# lamloei_app_a092500.net
KiCad netlist of a schematic drawn in EAGLE
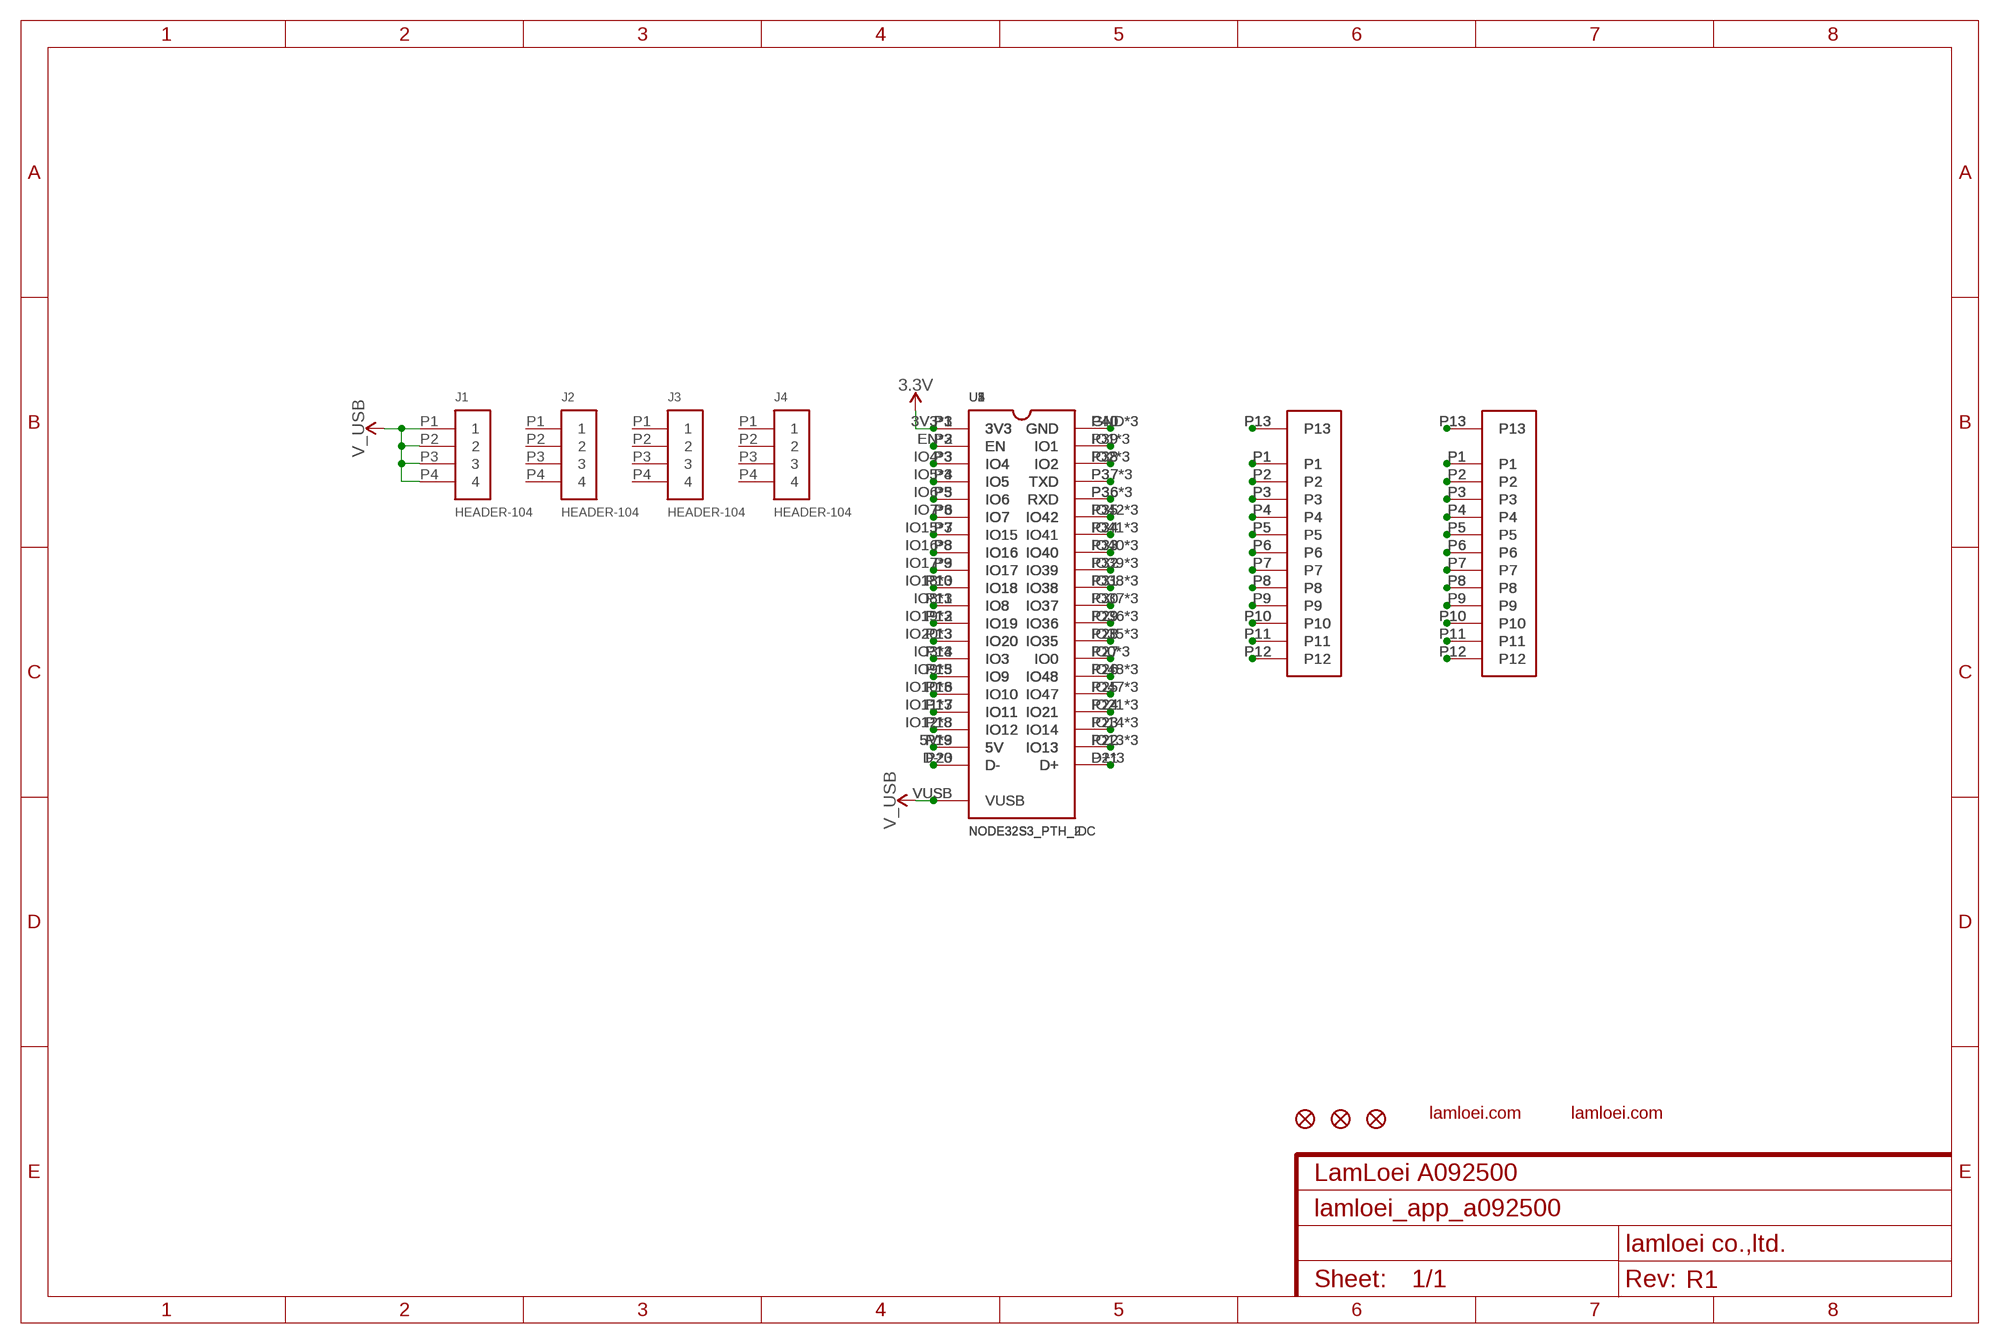
[diagram p0: schematic, sheet 1]

(export (version "E")
  (design (tool "Eeschema 10.0.6"))
  (components
    (comp (ref "J1")
      (value "HEADER-104")
      (footprint "eagle-import:HEADER-104")
      (libsource (lib "eagle-import") (part "HEADER-104"))
    )
    (comp (ref "J2")
      (value "HEADER-104")
      (footprint "eagle-import:HEADER-104")
      (libsource (lib "eagle-import") (part "HEADER-104"))
    )
    (comp (ref "J3")
      (value "HEADER-104")
      (footprint "eagle-import:HEADER-104")
      (libsource (lib "eagle-import") (part "HEADER-104"))
    )
    (comp (ref "J4")
      (value "HEADER-104")
      (footprint "eagle-import:HEADER-104")
      (libsource (lib "eagle-import") (part "HEADER-104"))
    )
    (comp (ref "U1")
      (value "NODE32S3_PTH_2")
      (footprint "eagle-import:NODE32S3_PTH_2")
      (libsource (lib "eagle-import") (part "NODE32S3_PTH_2"))
    )
    (comp (ref "U2")
      (value "NODE32S3_PTH_2")
      (footprint "eagle-import:NODE32S3_PTH_2")
      (libsource (lib "eagle-import") (part "NODE32S3_PTH_2"))
    )
    (comp (ref "U3")
      (value "NODE32S3_PTH_IDC")
      (footprint "eagle-import:NODE32S3_PTH_IDC")
      (libsource (lib "eagle-import") (part "NODE32S3_PTH_IDC"))
    )
    (comp (ref "U4")
      (value "NODE32S3_PTH_IDC")
      (footprint "eagle-import:NODE32S3_PTH_IDC")
      (libsource (lib "eagle-import") (part "NODE32S3_PTH_IDC"))
    )
    (comp (ref "U5")
      (value "NODE32S3_PTH_IDC")
      (footprint "eagle-import:NODE32S3_PTH_IDC")
      (libsource (lib "eagle-import") (part "NODE32S3_PTH_IDC"))
    )
    (comp (ref "X1")
      (value "5EHDRC-12P")
      (footprint "eagle-import:5EHDRC-12P")
      (libsource (lib "eagle-import") (part "5EHDRC-12P"))
    )
    (comp (ref "X2")
      (value "5EHDRC-12P-5.08MM")
      (footprint "eagle-import:5EHDRC-12P-5.08MM")
      (libsource (lib "eagle-import") (part "5EHDRC-12P-5.08MM"))
    )
    (comp (ref "X3")
      (value "5EHDRC-12P-2")
      (footprint "eagle-import:5EHDRC-12P-2")
      (libsource (lib "eagle-import") (part "5EHDRC-12P-2"))
    )
    (comp (ref "X4")
      (value "5EHDRC-12P")
      (footprint "eagle-import:5EHDRC-12P")
      (libsource (lib "eagle-import") (part "5EHDRC-12P"))
    )
    (comp (ref "X5")
      (value "5EHDRC-12P-5.08MM")
      (footprint "eagle-import:5EHDRC-12P-5.08MM")
      (libsource (lib "eagle-import") (part "5EHDRC-12P-5.08MM"))
    )
    (comp (ref "X6")
      (value "5EHDRC-12P-2")
      (footprint "eagle-import:5EHDRC-12P-2")
      (libsource (lib "eagle-import") (part "5EHDRC-12P-2"))
    )
    (comp (ref "ZFD1")
      (value "FIDUCIAL1X2")
      (footprint "eagle-import:FIDUCIAL-1X2")
      (libsource (lib "eagle-import") (part "FIDUCIAL1X2"))
    )
    (comp (ref "ZFD2")
      (value "FIDUCIAL1X2")
      (footprint "eagle-import:FIDUCIAL-1X2")
      (libsource (lib "eagle-import") (part "FIDUCIAL1X2"))
    )
    (comp (ref "ZFD3")
      (value "FIDUCIAL1X2")
      (footprint "eagle-import:FIDUCIAL-1X2")
      (libsource (lib "eagle-import") (part "FIDUCIAL1X2"))
    )
    (comp (ref "ZL1")
      (value "LAMLEOI_LOGO_3")
      (footprint "eagle-import:LAMLEOI_LOGO_3")
      (libsource (lib "eagle-import") (part "LAMLEOI_LOGO_3"))
    )
    (comp (ref "ZL2")
      (value "LAMLEOI_LOGO_3")
      (footprint "eagle-import:LAMLEOI_LOGO_3")
      (libsource (lib "eagle-import") (part "LAMLEOI_LOGO_3"))
    )
  )
  (nets
    (net (code "1") (name "3.3V") (class "Default")
      (node (ref "U1") (pin "3V3") (pinfunction "3V3_3V3") (pintype "bidirectional"))
      (node (ref "U1") (pin "P1") (pinfunction "3V3_P1") (pintype "bidirectional"))
      (node (ref "U1") (pin "Q1") (pinfunction "3V3_Q1") (pintype "bidirectional"))
      (node (ref "U2") (pin "3V3") (pinfunction "3V3_3V3") (pintype "bidirectional"))
      (node (ref "U2") (pin "P1") (pinfunction "3V3_P1") (pintype "bidirectional"))
      (node (ref "U2") (pin "Q1") (pinfunction "3V3_Q1") (pintype "bidirectional"))
      (node (ref "U3") (pin "P1") (pinfunction "3V3_P1") (pintype "bidirectional"))
      (node (ref "U4") (pin "P1") (pinfunction "3V3_P1") (pintype "bidirectional"))
      (node (ref "U5") (pin "P1") (pinfunction "3V3_P1") (pintype "bidirectional"))
    )
    (net (code "2") (name "Net-(U3-5V)") (class "Default")
      (node (ref "U1") (pin "5V") (pinfunction "5V_5V") (pintype "bidirectional"))
      (node (ref "U1") (pin "P19") (pinfunction "5V_P19") (pintype "bidirectional"))
      (node (ref "U1") (pin "Q19") (pinfunction "5V_Q19") (pintype "bidirectional"))
      (node (ref "U2") (pin "5V") (pinfunction "5V_5V") (pintype "bidirectional"))
      (node (ref "U2") (pin "P19") (pinfunction "5V_P19") (pintype "bidirectional"))
      (node (ref "U2") (pin "Q19") (pinfunction "5V_Q19") (pintype "bidirectional"))
      (node (ref "U3") (pin "P19") (pinfunction "5V_P19") (pintype "bidirectional"))
      (node (ref "U4") (pin "P19") (pinfunction "5V_P19") (pintype "bidirectional"))
      (node (ref "U5") (pin "P19") (pinfunction "5V_P19") (pintype "bidirectional"))
    )
    (net (code "3") (name "Net-(U3-D+)") (class "Default")
      (node (ref "U1") (pin "D+") (pinfunction "D+_D+") (pintype "bidirectional"))
      (node (ref "U1") (pin "P21") (pinfunction "D+_P21") (pintype "bidirectional"))
      (node (ref "U1") (pin "Q21") (pinfunction "D+_Q21") (pintype "bidirectional"))
      (node (ref "U2") (pin "D+") (pinfunction "D+_D+") (pintype "bidirectional"))
      (node (ref "U2") (pin "P21") (pinfunction "D+_P21") (pintype "bidirectional"))
      (node (ref "U2") (pin "Q21") (pinfunction "D+_Q21") (pintype "bidirectional"))
      (node (ref "U3") (pin "P21") (pinfunction "D+_P21") (pintype "bidirectional"))
      (node (ref "U4") (pin "P21") (pinfunction "D+_P21") (pintype "bidirectional"))
      (node (ref "U5") (pin "P21") (pinfunction "D+_P21") (pintype "bidirectional"))
    )
    (net (code "4") (name "Net-(U3-D-)") (class "Default")
      (node (ref "U1") (pin "D-") (pinfunction "D-_D-") (pintype "bidirectional"))
      (node (ref "U1") (pin "P20") (pinfunction "D-_P20") (pintype "bidirectional"))
      (node (ref "U1") (pin "Q20") (pinfunction "D-_Q20") (pintype "bidirectional"))
      (node (ref "U2") (pin "D-") (pinfunction "D-_D-") (pintype "bidirectional"))
      (node (ref "U2") (pin "P20") (pinfunction "D-_P20") (pintype "bidirectional"))
      (node (ref "U2") (pin "Q20") (pinfunction "D-_Q20") (pintype "bidirectional"))
      (node (ref "U3") (pin "P20") (pinfunction "D-_P20") (pintype "bidirectional"))
      (node (ref "U4") (pin "P20") (pinfunction "D-_P20") (pintype "bidirectional"))
      (node (ref "U5") (pin "P20") (pinfunction "D-_P20") (pintype "bidirectional"))
    )
    (net (code "5") (name "Net-(U3-EN)") (class "Default")
      (node (ref "U1") (pin "EN") (pinfunction "EN_EN") (pintype "bidirectional"))
      (node (ref "U1") (pin "P2") (pinfunction "EN_P2") (pintype "bidirectional"))
      (node (ref "U1") (pin "Q2") (pinfunction "EN_Q2") (pintype "bidirectional"))
      (node (ref "U2") (pin "EN") (pinfunction "EN_EN") (pintype "bidirectional"))
      (node (ref "U2") (pin "P2") (pinfunction "EN_P2") (pintype "bidirectional"))
      (node (ref "U2") (pin "Q2") (pinfunction "EN_Q2") (pintype "bidirectional"))
      (node (ref "U3") (pin "P2") (pinfunction "EN_P2") (pintype "bidirectional"))
      (node (ref "U4") (pin "P2") (pinfunction "EN_P2") (pintype "bidirectional"))
      (node (ref "U5") (pin "P2") (pinfunction "EN_P2") (pintype "bidirectional"))
    )
    (net (code "6") (name "Net-(U3-GND)") (class "Default")
      (node (ref "U1") (pin "GND") (pinfunction "GND_GND") (pintype "bidirectional"))
      (node (ref "U1") (pin "P40") (pinfunction "GND_P40") (pintype "bidirectional"))
      (node (ref "U1") (pin "Q40") (pinfunction "GND_Q40") (pintype "bidirectional"))
      (node (ref "U2") (pin "GND") (pinfunction "GND_GND") (pintype "bidirectional"))
      (node (ref "U2") (pin "P40") (pinfunction "GND_P40") (pintype "bidirectional"))
      (node (ref "U2") (pin "Q40") (pinfunction "GND_Q40") (pintype "bidirectional"))
      (node (ref "U3") (pin "P40") (pinfunction "GND_P40") (pintype "bidirectional"))
      (node (ref "U4") (pin "P40") (pinfunction "GND_P40") (pintype "bidirectional"))
      (node (ref "U5") (pin "P40") (pinfunction "GND_P40") (pintype "bidirectional"))
    )
    (net (code "7") (name "Net-(U3-IO0)") (class "Default")
      (node (ref "U1") (pin "IO0") (pinfunction "IO0_IO0") (pintype "bidirectional"))
      (node (ref "U1") (pin "P27") (pinfunction "IO0_P27") (pintype "bidirectional"))
      (node (ref "U1") (pin "Q27") (pinfunction "IO0_Q27") (pintype "bidirectional"))
      (node (ref "U2") (pin "IO0") (pinfunction "IO0_IO0") (pintype "bidirectional"))
      (node (ref "U2") (pin "P27") (pinfunction "IO0_P27") (pintype "bidirectional"))
      (node (ref "U2") (pin "Q27") (pinfunction "IO0_Q27") (pintype "bidirectional"))
      (node (ref "U3") (pin "P27") (pinfunction "IO0_P27") (pintype "bidirectional"))
      (node (ref "U4") (pin "P27") (pinfunction "IO0_P27") (pintype "bidirectional"))
      (node (ref "U5") (pin "P27") (pinfunction "IO0_P27") (pintype "bidirectional"))
    )
    (net (code "8") (name "Net-(U3-IO1)") (class "Default")
      (node (ref "U1") (pin "IO1") (pinfunction "IO1_IO1") (pintype "bidirectional"))
      (node (ref "U1") (pin "P39") (pinfunction "IO1_P39") (pintype "bidirectional"))
      (node (ref "U1") (pin "Q39") (pinfunction "IO1_Q39") (pintype "bidirectional"))
      (node (ref "U2") (pin "IO1") (pinfunction "IO1_IO1") (pintype "bidirectional"))
      (node (ref "U2") (pin "P39") (pinfunction "IO1_P39") (pintype "bidirectional"))
      (node (ref "U2") (pin "Q39") (pinfunction "IO1_Q39") (pintype "bidirectional"))
      (node (ref "U3") (pin "P39") (pinfunction "IO1_P39") (pintype "bidirectional"))
      (node (ref "U4") (pin "P39") (pinfunction "IO1_P39") (pintype "bidirectional"))
      (node (ref "U5") (pin "P39") (pinfunction "IO1_P39") (pintype "bidirectional"))
    )
    (net (code "9") (name "Net-(U3-IO2)") (class "Default")
      (node (ref "U1") (pin "IO2") (pinfunction "IO2_IO2") (pintype "bidirectional"))
      (node (ref "U1") (pin "P38") (pinfunction "IO2_P38") (pintype "bidirectional"))
      (node (ref "U1") (pin "Q38") (pinfunction "IO2_Q38") (pintype "bidirectional"))
      (node (ref "U2") (pin "IO2") (pinfunction "IO2_IO2") (pintype "bidirectional"))
      (node (ref "U2") (pin "P38") (pinfunction "IO2_P38") (pintype "bidirectional"))
      (node (ref "U2") (pin "Q38") (pinfunction "IO2_Q38") (pintype "bidirectional"))
      (node (ref "U3") (pin "P38") (pinfunction "IO2_P38") (pintype "bidirectional"))
      (node (ref "U4") (pin "P38") (pinfunction "IO2_P38") (pintype "bidirectional"))
      (node (ref "U5") (pin "P38") (pinfunction "IO2_P38") (pintype "bidirectional"))
    )
    (net (code "10") (name "Net-(U3-IO3)") (class "Default")
      (node (ref "U1") (pin "IO3") (pinfunction "IO3_IO3") (pintype "bidirectional"))
      (node (ref "U1") (pin "P14") (pinfunction "IO3_P14") (pintype "bidirectional"))
      (node (ref "U1") (pin "Q14") (pinfunction "IO3_Q14") (pintype "bidirectional"))
      (node (ref "U2") (pin "IO3") (pinfunction "IO3_IO3") (pintype "bidirectional"))
      (node (ref "U2") (pin "P14") (pinfunction "IO3_P14") (pintype "bidirectional"))
      (node (ref "U2") (pin "Q14") (pinfunction "IO3_Q14") (pintype "bidirectional"))
      (node (ref "U3") (pin "P14") (pinfunction "IO3_P14") (pintype "bidirectional"))
      (node (ref "U4") (pin "P14") (pinfunction "IO3_P14") (pintype "bidirectional"))
      (node (ref "U5") (pin "P14") (pinfunction "IO3_P14") (pintype "bidirectional"))
    )
    (net (code "11") (name "Net-(U3-IO4)") (class "Default")
      (node (ref "U1") (pin "IO4") (pinfunction "IO4_IO4") (pintype "bidirectional"))
      (node (ref "U1") (pin "P3") (pinfunction "IO4_P3") (pintype "bidirectional"))
      (node (ref "U1") (pin "Q3") (pinfunction "IO4_Q3") (pintype "bidirectional"))
      (node (ref "U2") (pin "IO4") (pinfunction "IO4_IO4") (pintype "bidirectional"))
      (node (ref "U2") (pin "P3") (pinfunction "IO4_P3") (pintype "bidirectional"))
      (node (ref "U2") (pin "Q3") (pinfunction "IO4_Q3") (pintype "bidirectional"))
      (node (ref "U3") (pin "P3") (pinfunction "IO4_P3") (pintype "bidirectional"))
      (node (ref "U4") (pin "P3") (pinfunction "IO4_P3") (pintype "bidirectional"))
      (node (ref "U5") (pin "P3") (pinfunction "IO4_P3") (pintype "bidirectional"))
    )
    (net (code "12") (name "Net-(U3-IO5)") (class "Default")
      (node (ref "U1") (pin "IO5") (pinfunction "IO5_IO5") (pintype "bidirectional"))
      (node (ref "U1") (pin "P4") (pinfunction "IO5_P4") (pintype "bidirectional"))
      (node (ref "U1") (pin "Q4") (pinfunction "IO5_Q4") (pintype "bidirectional"))
      (node (ref "U2") (pin "IO5") (pinfunction "IO5_IO5") (pintype "bidirectional"))
      (node (ref "U2") (pin "P4") (pinfunction "IO5_P4") (pintype "bidirectional"))
      (node (ref "U2") (pin "Q4") (pinfunction "IO5_Q4") (pintype "bidirectional"))
      (node (ref "U3") (pin "P4") (pinfunction "IO5_P4") (pintype "bidirectional"))
      (node (ref "U4") (pin "P4") (pinfunction "IO5_P4") (pintype "bidirectional"))
      (node (ref "U5") (pin "P4") (pinfunction "IO5_P4") (pintype "bidirectional"))
    )
    (net (code "13") (name "Net-(U3-IO6)") (class "Default")
      (node (ref "U1") (pin "IO6") (pinfunction "IO6_IO6") (pintype "bidirectional"))
      (node (ref "U1") (pin "P5") (pinfunction "IO6_P5") (pintype "bidirectional"))
      (node (ref "U1") (pin "Q5") (pinfunction "IO6_Q5") (pintype "bidirectional"))
      (node (ref "U2") (pin "IO6") (pinfunction "IO6_IO6") (pintype "bidirectional"))
      (node (ref "U2") (pin "P5") (pinfunction "IO6_P5") (pintype "bidirectional"))
      (node (ref "U2") (pin "Q5") (pinfunction "IO6_Q5") (pintype "bidirectional"))
      (node (ref "U3") (pin "P5") (pinfunction "IO6_P5") (pintype "bidirectional"))
      (node (ref "U4") (pin "P5") (pinfunction "IO6_P5") (pintype "bidirectional"))
      (node (ref "U5") (pin "P5") (pinfunction "IO6_P5") (pintype "bidirectional"))
    )
    (net (code "14") (name "Net-(U3-IO7)") (class "Default")
      (node (ref "U1") (pin "IO7") (pinfunction "IO7_IO7") (pintype "bidirectional"))
      (node (ref "U1") (pin "P6") (pinfunction "IO7_P6") (pintype "bidirectional"))
      (node (ref "U1") (pin "Q6") (pinfunction "IO7_Q6") (pintype "bidirectional"))
      (node (ref "U2") (pin "IO7") (pinfunction "IO7_IO7") (pintype "bidirectional"))
      (node (ref "U2") (pin "P6") (pinfunction "IO7_P6") (pintype "bidirectional"))
      (node (ref "U2") (pin "Q6") (pinfunction "IO7_Q6") (pintype "bidirectional"))
      (node (ref "U3") (pin "P6") (pinfunction "IO7_P6") (pintype "bidirectional"))
      (node (ref "U4") (pin "P6") (pinfunction "IO7_P6") (pintype "bidirectional"))
      (node (ref "U5") (pin "P6") (pinfunction "IO7_P6") (pintype "bidirectional"))
    )
    (net (code "15") (name "Net-(U3-IO8)") (class "Default")
      (node (ref "U1") (pin "IO8") (pinfunction "IO8_IO8") (pintype "bidirectional"))
      (node (ref "U1") (pin "P11") (pinfunction "IO8_P11") (pintype "bidirectional"))
      (node (ref "U1") (pin "Q11") (pinfunction "IO8_Q11") (pintype "bidirectional"))
      (node (ref "U2") (pin "IO8") (pinfunction "IO8_IO8") (pintype "bidirectional"))
      (node (ref "U2") (pin "P11") (pinfunction "IO8_P11") (pintype "bidirectional"))
      (node (ref "U2") (pin "Q11") (pinfunction "IO8_Q11") (pintype "bidirectional"))
      (node (ref "U3") (pin "P11") (pinfunction "IO8_P11") (pintype "bidirectional"))
      (node (ref "U4") (pin "P11") (pinfunction "IO8_P11") (pintype "bidirectional"))
      (node (ref "U5") (pin "P11") (pinfunction "IO8_P11") (pintype "bidirectional"))
    )
    (net (code "16") (name "Net-(U3-IO9)") (class "Default")
      (node (ref "U1") (pin "IO9") (pinfunction "IO9_IO9") (pintype "bidirectional"))
      (node (ref "U1") (pin "P15") (pinfunction "IO9_P15") (pintype "bidirectional"))
      (node (ref "U1") (pin "Q15") (pinfunction "IO9_Q15") (pintype "bidirectional"))
      (node (ref "U2") (pin "IO9") (pinfunction "IO9_IO9") (pintype "bidirectional"))
      (node (ref "U2") (pin "P15") (pinfunction "IO9_P15") (pintype "bidirectional"))
      (node (ref "U2") (pin "Q15") (pinfunction "IO9_Q15") (pintype "bidirectional"))
      (node (ref "U3") (pin "P15") (pinfunction "IO9_P15") (pintype "bidirectional"))
      (node (ref "U4") (pin "P15") (pinfunction "IO9_P15") (pintype "bidirectional"))
      (node (ref "U5") (pin "P15") (pinfunction "IO9_P15") (pintype "bidirectional"))
    )
    (net (code "17") (name "Net-(U3-IO10)") (class "Default")
      (node (ref "U1") (pin "IO10") (pinfunction "IO10_IO10") (pintype "bidirectional"))
      (node (ref "U1") (pin "P16") (pinfunction "IO10_P16") (pintype "bidirectional"))
      (node (ref "U1") (pin "Q16") (pinfunction "IO10_Q16") (pintype "bidirectional"))
      (node (ref "U2") (pin "IO10") (pinfunction "IO10_IO10") (pintype "bidirectional"))
      (node (ref "U2") (pin "P16") (pinfunction "IO10_P16") (pintype "bidirectional"))
      (node (ref "U2") (pin "Q16") (pinfunction "IO10_Q16") (pintype "bidirectional"))
      (node (ref "U3") (pin "P16") (pinfunction "IO10_P16") (pintype "bidirectional"))
      (node (ref "U4") (pin "P16") (pinfunction "IO10_P16") (pintype "bidirectional"))
      (node (ref "U5") (pin "P16") (pinfunction "IO10_P16") (pintype "bidirectional"))
    )
    (net (code "18") (name "Net-(U3-IO11)") (class "Default")
      (node (ref "U1") (pin "IO11") (pinfunction "IO11_IO11") (pintype "bidirectional"))
      (node (ref "U1") (pin "P17") (pinfunction "IO11_P17") (pintype "bidirectional"))
      (node (ref "U1") (pin "Q17") (pinfunction "IO11_Q17") (pintype "bidirectional"))
      (node (ref "U2") (pin "IO11") (pinfunction "IO11_IO11") (pintype "bidirectional"))
      (node (ref "U2") (pin "P17") (pinfunction "IO11_P17") (pintype "bidirectional"))
      (node (ref "U2") (pin "Q17") (pinfunction "IO11_Q17") (pintype "bidirectional"))
      (node (ref "U3") (pin "P17") (pinfunction "IO11_P17") (pintype "bidirectional"))
      (node (ref "U4") (pin "P17") (pinfunction "IO11_P17") (pintype "bidirectional"))
      (node (ref "U5") (pin "P17") (pinfunction "IO11_P17") (pintype "bidirectional"))
    )
    (net (code "19") (name "Net-(U3-IO12)") (class "Default")
      (node (ref "U1") (pin "IO12") (pinfunction "IO12_IO12") (pintype "bidirectional"))
      (node (ref "U1") (pin "P18") (pinfunction "IO12_P18") (pintype "bidirectional"))
      (node (ref "U1") (pin "Q18") (pinfunction "IO12_Q18") (pintype "bidirectional"))
      (node (ref "U2") (pin "IO12") (pinfunction "IO12_IO12") (pintype "bidirectional"))
      (node (ref "U2") (pin "P18") (pinfunction "IO12_P18") (pintype "bidirectional"))
      (node (ref "U2") (pin "Q18") (pinfunction "IO12_Q18") (pintype "bidirectional"))
      (node (ref "U3") (pin "P18") (pinfunction "IO12_P18") (pintype "bidirectional"))
      (node (ref "U4") (pin "P18") (pinfunction "IO12_P18") (pintype "bidirectional"))
      (node (ref "U5") (pin "P18") (pinfunction "IO12_P18") (pintype "bidirectional"))
    )
    (net (code "20") (name "Net-(U3-IO13)") (class "Default")
      (node (ref "U1") (pin "IO13") (pinfunction "IO13_IO13") (pintype "bidirectional"))
      (node (ref "U1") (pin "P22") (pinfunction "IO13_P22") (pintype "bidirectional"))
      (node (ref "U1") (pin "Q22") (pinfunction "IO13_Q22") (pintype "bidirectional"))
      (node (ref "U2") (pin "IO13") (pinfunction "IO13_IO13") (pintype "bidirectional"))
      (node (ref "U2") (pin "P22") (pinfunction "IO13_P22") (pintype "bidirectional"))
      (node (ref "U2") (pin "Q22") (pinfunction "IO13_Q22") (pintype "bidirectional"))
      (node (ref "U3") (pin "P22") (pinfunction "IO13_P22") (pintype "bidirectional"))
      (node (ref "U4") (pin "P22") (pinfunction "IO13_P22") (pintype "bidirectional"))
      (node (ref "U5") (pin "P22") (pinfunction "IO13_P22") (pintype "bidirectional"))
    )
    (net (code "21") (name "Net-(U3-IO14)") (class "Default")
      (node (ref "U1") (pin "IO14") (pinfunction "IO14_IO14") (pintype "bidirectional"))
      (node (ref "U1") (pin "P23") (pinfunction "IO14_P23") (pintype "bidirectional"))
      (node (ref "U1") (pin "Q23") (pinfunction "IO14_Q23") (pintype "bidirectional"))
      (node (ref "U2") (pin "IO14") (pinfunction "IO14_IO14") (pintype "bidirectional"))
      (node (ref "U2") (pin "P23") (pinfunction "IO14_P23") (pintype "bidirectional"))
      (node (ref "U2") (pin "Q23") (pinfunction "IO14_Q23") (pintype "bidirectional"))
      (node (ref "U3") (pin "P23") (pinfunction "IO14_P23") (pintype "bidirectional"))
      (node (ref "U4") (pin "P23") (pinfunction "IO14_P23") (pintype "bidirectional"))
      (node (ref "U5") (pin "P23") (pinfunction "IO14_P23") (pintype "bidirectional"))
    )
    (net (code "22") (name "Net-(U3-IO15)") (class "Default")
      (node (ref "U1") (pin "IO15") (pinfunction "IO15_IO15") (pintype "bidirectional"))
      (node (ref "U1") (pin "P7") (pinfunction "IO15_P7") (pintype "bidirectional"))
      (node (ref "U1") (pin "Q7") (pinfunction "IO15_Q7") (pintype "bidirectional"))
      (node (ref "U2") (pin "IO15") (pinfunction "IO15_IO15") (pintype "bidirectional"))
      (node (ref "U2") (pin "P7") (pinfunction "IO15_P7") (pintype "bidirectional"))
      (node (ref "U2") (pin "Q7") (pinfunction "IO15_Q7") (pintype "bidirectional"))
      (node (ref "U3") (pin "P7") (pinfunction "IO15_P7") (pintype "bidirectional"))
      (node (ref "U4") (pin "P7") (pinfunction "IO15_P7") (pintype "bidirectional"))
      (node (ref "U5") (pin "P7") (pinfunction "IO15_P7") (pintype "bidirectional"))
    )
    (net (code "23") (name "Net-(U3-IO16)") (class "Default")
      (node (ref "U1") (pin "IO16") (pinfunction "IO16_IO16") (pintype "bidirectional"))
      (node (ref "U1") (pin "P8") (pinfunction "IO16_P8") (pintype "bidirectional"))
      (node (ref "U1") (pin "Q8") (pinfunction "IO16_Q8") (pintype "bidirectional"))
      (node (ref "U2") (pin "IO16") (pinfunction "IO16_IO16") (pintype "bidirectional"))
      (node (ref "U2") (pin "P8") (pinfunction "IO16_P8") (pintype "bidirectional"))
      (node (ref "U2") (pin "Q8") (pinfunction "IO16_Q8") (pintype "bidirectional"))
      (node (ref "U3") (pin "P8") (pinfunction "IO16_P8") (pintype "bidirectional"))
      (node (ref "U4") (pin "P8") (pinfunction "IO16_P8") (pintype "bidirectional"))
      (node (ref "U5") (pin "P8") (pinfunction "IO16_P8") (pintype "bidirectional"))
    )
    (net (code "24") (name "Net-(U3-IO17)") (class "Default")
      (node (ref "U1") (pin "IO17") (pinfunction "IO17_IO17") (pintype "bidirectional"))
      (node (ref "U1") (pin "P9") (pinfunction "IO17_P9") (pintype "bidirectional"))
      (node (ref "U1") (pin "Q9") (pinfunction "IO17_Q9") (pintype "bidirectional"))
      (node (ref "U2") (pin "IO17") (pinfunction "IO17_IO17") (pintype "bidirectional"))
      (node (ref "U2") (pin "P9") (pinfunction "IO17_P9") (pintype "bidirectional"))
      (node (ref "U2") (pin "Q9") (pinfunction "IO17_Q9") (pintype "bidirectional"))
      (node (ref "U3") (pin "P9") (pinfunction "IO17_P9") (pintype "bidirectional"))
      (node (ref "U4") (pin "P9") (pinfunction "IO17_P9") (pintype "bidirectional"))
      (node (ref "U5") (pin "P9") (pinfunction "IO17_P9") (pintype "bidirectional"))
    )
    (net (code "25") (name "Net-(U3-IO18)") (class "Default")
      (node (ref "U1") (pin "IO18") (pinfunction "IO18_IO18") (pintype "bidirectional"))
      (node (ref "U1") (pin "P10") (pinfunction "IO18_P10") (pintype "bidirectional"))
      (node (ref "U1") (pin "Q10") (pinfunction "IO18_Q10") (pintype "bidirectional"))
      (node (ref "U2") (pin "IO18") (pinfunction "IO18_IO18") (pintype "bidirectional"))
      (node (ref "U2") (pin "P10") (pinfunction "IO18_P10") (pintype "bidirectional"))
      (node (ref "U2") (pin "Q10") (pinfunction "IO18_Q10") (pintype "bidirectional"))
      (node (ref "U3") (pin "P10") (pinfunction "IO18_P10") (pintype "bidirectional"))
      (node (ref "U4") (pin "P10") (pinfunction "IO18_P10") (pintype "bidirectional"))
      (node (ref "U5") (pin "P10") (pinfunction "IO18_P10") (pintype "bidirectional"))
    )
    (net (code "26") (name "Net-(U3-IO19)") (class "Default")
      (node (ref "U1") (pin "IO19") (pinfunction "IO19_IO19") (pintype "bidirectional"))
      (node (ref "U1") (pin "P12") (pinfunction "IO19_P12") (pintype "bidirectional"))
      (node (ref "U1") (pin "Q12") (pinfunction "IO19_Q12") (pintype "bidirectional"))
      (node (ref "U2") (pin "IO19") (pinfunction "IO19_IO19") (pintype "bidirectional"))
      (node (ref "U2") (pin "P12") (pinfunction "IO19_P12") (pintype "bidirectional"))
      (node (ref "U2") (pin "Q12") (pinfunction "IO19_Q12") (pintype "bidirectional"))
      (node (ref "U3") (pin "P12") (pinfunction "IO19_P12") (pintype "bidirectional"))
      (node (ref "U4") (pin "P12") (pinfunction "IO19_P12") (pintype "bidirectional"))
      (node (ref "U5") (pin "P12") (pinfunction "IO19_P12") (pintype "bidirectional"))
    )
    (net (code "27") (name "Net-(U3-IO20)") (class "Default")
      (node (ref "U1") (pin "IO20") (pinfunction "IO20_IO20") (pintype "bidirectional"))
      (node (ref "U1") (pin "P13") (pinfunction "IO20_P13") (pintype "bidirectional"))
      (node (ref "U1") (pin "Q13") (pinfunction "IO20_Q13") (pintype "bidirectional"))
      (node (ref "U2") (pin "IO20") (pinfunction "IO20_IO20") (pintype "bidirectional"))
      (node (ref "U2") (pin "P13") (pinfunction "IO20_P13") (pintype "bidirectional"))
      (node (ref "U2") (pin "Q13") (pinfunction "IO20_Q13") (pintype "bidirectional"))
      (node (ref "U3") (pin "P13") (pinfunction "IO20_P13") (pintype "bidirectional"))
      (node (ref "U4") (pin "P13") (pinfunction "IO20_P13") (pintype "bidirectional"))
      (node (ref "U5") (pin "P13") (pinfunction "IO20_P13") (pintype "bidirectional"))
    )
    (net (code "28") (name "Net-(U3-IO21)") (class "Default")
      (node (ref "U1") (pin "IO21") (pinfunction "IO21_IO21") (pintype "bidirectional"))
      (node (ref "U1") (pin "P24") (pinfunction "IO21_P24") (pintype "bidirectional"))
      (node (ref "U1") (pin "Q24") (pinfunction "IO21_Q24") (pintype "bidirectional"))
      (node (ref "U2") (pin "IO21") (pinfunction "IO21_IO21") (pintype "bidirectional"))
      (node (ref "U2") (pin "P24") (pinfunction "IO21_P24") (pintype "bidirectional"))
      (node (ref "U2") (pin "Q24") (pinfunction "IO21_Q24") (pintype "bidirectional"))
      (node (ref "U3") (pin "P24") (pinfunction "IO21_P24") (pintype "bidirectional"))
      (node (ref "U4") (pin "P24") (pinfunction "IO21_P24") (pintype "bidirectional"))
      (node (ref "U5") (pin "P24") (pinfunction "IO21_P24") (pintype "bidirectional"))
    )
    (net (code "29") (name "Net-(U3-IO35)") (class "Default")
      (node (ref "U1") (pin "IO35") (pinfunction "IO35_IO35") (pintype "bidirectional"))
      (node (ref "U1") (pin "P28") (pinfunction "IO35_P28") (pintype "bidirectional"))
      (node (ref "U1") (pin "Q28") (pinfunction "IO35_Q28") (pintype "bidirectional"))
      (node (ref "U2") (pin "IO35") (pinfunction "IO35_IO35") (pintype "bidirectional"))
      (node (ref "U2") (pin "P28") (pinfunction "IO35_P28") (pintype "bidirectional"))
      (node (ref "U2") (pin "Q28") (pinfunction "IO35_Q28") (pintype "bidirectional"))
      (node (ref "U3") (pin "P28") (pinfunction "IO35_P28") (pintype "bidirectional"))
      (node (ref "U4") (pin "P28") (pinfunction "IO35_P28") (pintype "bidirectional"))
      (node (ref "U5") (pin "P28") (pinfunction "IO35_P28") (pintype "bidirectional"))
    )
    (net (code "30") (name "Net-(U3-IO36)") (class "Default")
      (node (ref "U1") (pin "IO36") (pinfunction "IO36_IO36") (pintype "bidirectional"))
      (node (ref "U1") (pin "P29") (pinfunction "IO36_P29") (pintype "bidirectional"))
      (node (ref "U1") (pin "Q29") (pinfunction "IO36_Q29") (pintype "bidirectional"))
      (node (ref "U2") (pin "IO36") (pinfunction "IO36_IO36") (pintype "bidirectional"))
      (node (ref "U2") (pin "P29") (pinfunction "IO36_P29") (pintype "bidirectional"))
      (node (ref "U2") (pin "Q29") (pinfunction "IO36_Q29") (pintype "bidirectional"))
      (node (ref "U3") (pin "P29") (pinfunction "IO36_P29") (pintype "bidirectional"))
      (node (ref "U4") (pin "P29") (pinfunction "IO36_P29") (pintype "bidirectional"))
      (node (ref "U5") (pin "P29") (pinfunction "IO36_P29") (pintype "bidirectional"))
    )
    (net (code "31") (name "Net-(U3-IO37)") (class "Default")
      (node (ref "U1") (pin "IO37") (pinfunction "IO37_IO37") (pintype "bidirectional"))
      (node (ref "U1") (pin "P30") (pinfunction "IO37_P30") (pintype "bidirectional"))
      (node (ref "U1") (pin "Q30") (pinfunction "IO37_Q30") (pintype "bidirectional"))
      (node (ref "U2") (pin "IO37") (pinfunction "IO37_IO37") (pintype "bidirectional"))
      (node (ref "U2") (pin "P30") (pinfunction "IO37_P30") (pintype "bidirectional"))
      (node (ref "U2") (pin "Q30") (pinfunction "IO37_Q30") (pintype "bidirectional"))
      (node (ref "U3") (pin "P30") (pinfunction "IO37_P30") (pintype "bidirectional"))
      (node (ref "U4") (pin "P30") (pinfunction "IO37_P30") (pintype "bidirectional"))
      (node (ref "U5") (pin "P30") (pinfunction "IO37_P30") (pintype "bidirectional"))
    )
    (net (code "32") (name "Net-(U3-IO38)") (class "Default")
      (node (ref "U1") (pin "IO38") (pinfunction "IO38_IO38") (pintype "bidirectional"))
      (node (ref "U1") (pin "P31") (pinfunction "IO38_P31") (pintype "bidirectional"))
      (node (ref "U1") (pin "Q31") (pinfunction "IO38_Q31") (pintype "bidirectional"))
      (node (ref "U2") (pin "IO38") (pinfunction "IO38_IO38") (pintype "bidirectional"))
      (node (ref "U2") (pin "P31") (pinfunction "IO38_P31") (pintype "bidirectional"))
      (node (ref "U2") (pin "Q31") (pinfunction "IO38_Q31") (pintype "bidirectional"))
      (node (ref "U3") (pin "P31") (pinfunction "IO38_P31") (pintype "bidirectional"))
      (node (ref "U4") (pin "P31") (pinfunction "IO38_P31") (pintype "bidirectional"))
      (node (ref "U5") (pin "P31") (pinfunction "IO38_P31") (pintype "bidirectional"))
    )
    (net (code "33") (name "Net-(U3-IO39)") (class "Default")
      (node (ref "U1") (pin "IO39") (pinfunction "IO39_IO39") (pintype "bidirectional"))
      (node (ref "U1") (pin "P32") (pinfunction "IO39_P32") (pintype "bidirectional"))
      (node (ref "U1") (pin "Q32") (pinfunction "IO39_Q32") (pintype "bidirectional"))
      (node (ref "U2") (pin "IO39") (pinfunction "IO39_IO39") (pintype "bidirectional"))
      (node (ref "U2") (pin "P32") (pinfunction "IO39_P32") (pintype "bidirectional"))
      (node (ref "U2") (pin "Q32") (pinfunction "IO39_Q32") (pintype "bidirectional"))
      (node (ref "U3") (pin "P32") (pinfunction "IO39_P32") (pintype "bidirectional"))
      (node (ref "U4") (pin "P32") (pinfunction "IO39_P32") (pintype "bidirectional"))
      (node (ref "U5") (pin "P32") (pinfunction "IO39_P32") (pintype "bidirectional"))
    )
    (net (code "34") (name "Net-(U3-IO40)") (class "Default")
      (node (ref "U1") (pin "IO40") (pinfunction "IO40_IO40") (pintype "bidirectional"))
      (node (ref "U1") (pin "P33") (pinfunction "IO40_P33") (pintype "bidirectional"))
      (node (ref "U1") (pin "Q33") (pinfunction "IO40_Q33") (pintype "bidirectional"))
      (node (ref "U2") (pin "IO40") (pinfunction "IO40_IO40") (pintype "bidirectional"))
      (node (ref "U2") (pin "P33") (pinfunction "IO40_P33") (pintype "bidirectional"))
      (node (ref "U2") (pin "Q33") (pinfunction "IO40_Q33") (pintype "bidirectional"))
      (node (ref "U3") (pin "P33") (pinfunction "IO40_P33") (pintype "bidirectional"))
      (node (ref "U4") (pin "P33") (pinfunction "IO40_P33") (pintype "bidirectional"))
      (node (ref "U5") (pin "P33") (pinfunction "IO40_P33") (pintype "bidirectional"))
    )
    (net (code "35") (name "Net-(U3-IO41)") (class "Default")
      (node (ref "U1") (pin "IO41") (pinfunction "IO41_IO41") (pintype "bidirectional"))
      (node (ref "U1") (pin "P34") (pinfunction "IO41_P34") (pintype "bidirectional"))
      (node (ref "U1") (pin "Q34") (pinfunction "IO41_Q34") (pintype "bidirectional"))
      (node (ref "U2") (pin "IO41") (pinfunction "IO41_IO41") (pintype "bidirectional"))
      (node (ref "U2") (pin "P34") (pinfunction "IO41_P34") (pintype "bidirectional"))
      (node (ref "U2") (pin "Q34") (pinfunction "IO41_Q34") (pintype "bidirectional"))
      (node (ref "U3") (pin "P34") (pinfunction "IO41_P34") (pintype "bidirectional"))
      (node (ref "U4") (pin "P34") (pinfunction "IO41_P34") (pintype "bidirectional"))
      (node (ref "U5") (pin "P34") (pinfunction "IO41_P34") (pintype "bidirectional"))
    )
    (net (code "36") (name "Net-(U3-IO42)") (class "Default")
      (node (ref "U1") (pin "IO42") (pinfunction "IO42_IO42") (pintype "bidirectional"))
      (node (ref "U1") (pin "P35") (pinfunction "IO42_P35") (pintype "bidirectional"))
      (node (ref "U1") (pin "Q35") (pinfunction "IO42_Q35") (pintype "bidirectional"))
      (node (ref "U2") (pin "IO42") (pinfunction "IO42_IO42") (pintype "bidirectional"))
      (node (ref "U2") (pin "P35") (pinfunction "IO42_P35") (pintype "bidirectional"))
      (node (ref "U2") (pin "Q35") (pinfunction "IO42_Q35") (pintype "bidirectional"))
      (node (ref "U3") (pin "P35") (pinfunction "IO42_P35") (pintype "bidirectional"))
      (node (ref "U4") (pin "P35") (pinfunction "IO42_P35") (pintype "bidirectional"))
      (node (ref "U5") (pin "P35") (pinfunction "IO42_P35") (pintype "bidirectional"))
    )
    (net (code "37") (name "Net-(U3-IO47)") (class "Default")
      (node (ref "U1") (pin "IO47") (pinfunction "IO47_IO47") (pintype "bidirectional"))
      (node (ref "U1") (pin "P25") (pinfunction "IO47_P25") (pintype "bidirectional"))
      (node (ref "U1") (pin "Q25") (pinfunction "IO47_Q25") (pintype "bidirectional"))
      (node (ref "U2") (pin "IO47") (pinfunction "IO47_IO47") (pintype "bidirectional"))
      (node (ref "U2") (pin "P25") (pinfunction "IO47_P25") (pintype "bidirectional"))
      (node (ref "U2") (pin "Q25") (pinfunction "IO47_Q25") (pintype "bidirectional"))
      (node (ref "U3") (pin "P25") (pinfunction "IO47_P25") (pintype "bidirectional"))
      (node (ref "U4") (pin "P25") (pinfunction "IO47_P25") (pintype "bidirectional"))
      (node (ref "U5") (pin "P25") (pinfunction "IO47_P25") (pintype "bidirectional"))
    )
    (net (code "38") (name "Net-(U3-IO48)") (class "Default")
      (node (ref "U1") (pin "IO48") (pinfunction "IO48_IO48") (pintype "bidirectional"))
      (node (ref "U1") (pin "P26") (pinfunction "IO48_P26") (pintype "bidirectional"))
      (node (ref "U1") (pin "Q26") (pinfunction "IO48_Q26") (pintype "bidirectional"))
      (node (ref "U2") (pin "IO48") (pinfunction "IO48_IO48") (pintype "bidirectional"))
      (node (ref "U2") (pin "P26") (pinfunction "IO48_P26") (pintype "bidirectional"))
      (node (ref "U2") (pin "Q26") (pinfunction "IO48_Q26") (pintype "bidirectional"))
      (node (ref "U3") (pin "P26") (pinfunction "IO48_P26") (pintype "bidirectional"))
      (node (ref "U4") (pin "P26") (pinfunction "IO48_P26") (pintype "bidirectional"))
      (node (ref "U5") (pin "P26") (pinfunction "IO48_P26") (pintype "bidirectional"))
    )
    (net (code "39") (name "Net-(U3-RXD)") (class "Default")
      (node (ref "U1") (pin "P36") (pinfunction "RXD_P36") (pintype "bidirectional"))
      (node (ref "U1") (pin "Q36") (pinfunction "RXD_Q36") (pintype "bidirectional"))
      (node (ref "U1") (pin "RXD") (pinfunction "RXD_RXD") (pintype "bidirectional"))
      (node (ref "U2") (pin "P36") (pinfunction "RXD_P36") (pintype "bidirectional"))
      (node (ref "U2") (pin "Q36") (pinfunction "RXD_Q36") (pintype "bidirectional"))
      (node (ref "U2") (pin "RXD") (pinfunction "RXD_RXD") (pintype "bidirectional"))
      (node (ref "U3") (pin "P36") (pinfunction "RXD_P36") (pintype "bidirectional"))
      (node (ref "U4") (pin "P36") (pinfunction "RXD_P36") (pintype "bidirectional"))
      (node (ref "U5") (pin "P36") (pinfunction "RXD_P36") (pintype "bidirectional"))
    )
    (net (code "40") (name "Net-(U3-TXD)") (class "Default")
      (node (ref "U1") (pin "P37") (pinfunction "TXD_P37") (pintype "bidirectional"))
      (node (ref "U1") (pin "Q37") (pinfunction "TXD_Q37") (pintype "bidirectional"))
      (node (ref "U1") (pin "TXD") (pinfunction "TXD_TXD") (pintype "bidirectional"))
      (node (ref "U2") (pin "P37") (pinfunction "TXD_P37") (pintype "bidirectional"))
      (node (ref "U2") (pin "Q37") (pinfunction "TXD_Q37") (pintype "bidirectional"))
      (node (ref "U2") (pin "TXD") (pinfunction "TXD_TXD") (pintype "bidirectional"))
      (node (ref "U3") (pin "P37") (pinfunction "TXD_P37") (pintype "bidirectional"))
      (node (ref "U4") (pin "P37") (pinfunction "TXD_P37") (pintype "bidirectional"))
      (node (ref "U5") (pin "P37") (pinfunction "TXD_P37") (pintype "bidirectional"))
    )
    (net (code "41") (name "Net-(X1-PadP1)") (class "Default")
      (node (ref "X1") (pin "P1") (pinfunction "P1_P1") (pintype "bidirectional"))
      (node (ref "X2") (pin "P1") (pinfunction "P1_P1") (pintype "bidirectional"))
      (node (ref "X3") (pin "P1") (pinfunction "P1_P1") (pintype "bidirectional"))
    )
    (net (code "42") (name "Net-(X1-PadP2)") (class "Default")
      (node (ref "X1") (pin "P2") (pinfunction "P2_P2") (pintype "bidirectional"))
      (node (ref "X2") (pin "P2") (pinfunction "P2_P2") (pintype "bidirectional"))
      (node (ref "X3") (pin "P2") (pinfunction "P2_P2") (pintype "bidirectional"))
    )
    (net (code "43") (name "Net-(X1-PadP3)") (class "Default")
      (node (ref "X1") (pin "P3") (pinfunction "P3_P3") (pintype "bidirectional"))
      (node (ref "X2") (pin "P3") (pinfunction "P3_P3") (pintype "bidirectional"))
      (node (ref "X3") (pin "P3") (pinfunction "P3_P3") (pintype "bidirectional"))
    )
    (net (code "44") (name "Net-(X1-PadP4)") (class "Default")
      (node (ref "X1") (pin "P4") (pinfunction "P4_P4") (pintype "bidirectional"))
      (node (ref "X2") (pin "P4") (pinfunction "P4_P4") (pintype "bidirectional"))
      (node (ref "X3") (pin "P4") (pinfunction "P4_P4") (pintype "bidirectional"))
    )
    (net (code "45") (name "Net-(X1-PadP5)") (class "Default")
      (node (ref "X1") (pin "P5") (pinfunction "P5_P5") (pintype "bidirectional"))
      (node (ref "X2") (pin "P5") (pinfunction "P5_P5") (pintype "bidirectional"))
      (node (ref "X3") (pin "P5") (pinfunction "P5_P5") (pintype "bidirectional"))
    )
    (net (code "46") (name "Net-(X1-PadP6)") (class "Default")
      (node (ref "X1") (pin "P6") (pinfunction "P6_P6") (pintype "bidirectional"))
      (node (ref "X2") (pin "P6") (pinfunction "P6_P6") (pintype "bidirectional"))
      (node (ref "X3") (pin "P6") (pinfunction "P6_P6") (pintype "bidirectional"))
    )
    (net (code "47") (name "Net-(X1-PadP7)") (class "Default")
      (node (ref "X1") (pin "P7") (pinfunction "P7_P7") (pintype "bidirectional"))
      (node (ref "X2") (pin "P7") (pinfunction "P7_P7") (pintype "bidirectional"))
      (node (ref "X3") (pin "P7") (pinfunction "P7_P7") (pintype "bidirectional"))
    )
    (net (code "48") (name "Net-(X1-PadP8)") (class "Default")
      (node (ref "X1") (pin "P8") (pinfunction "P8_P8") (pintype "bidirectional"))
      (node (ref "X2") (pin "P8") (pinfunction "P8_P8") (pintype "bidirectional"))
      (node (ref "X3") (pin "P8") (pinfunction "P8_P8") (pintype "bidirectional"))
    )
    (net (code "49") (name "Net-(X1-PadP9)") (class "Default")
      (node (ref "X1") (pin "P9") (pinfunction "P9_P9") (pintype "bidirectional"))
      (node (ref "X2") (pin "P9") (pinfunction "P9_P9") (pintype "bidirectional"))
      (node (ref "X3") (pin "P9") (pinfunction "P9_P9") (pintype "bidirectional"))
    )
    (net (code "50") (name "Net-(X1-PadP10)") (class "Default")
      (node (ref "X1") (pin "P10") (pinfunction "P10_P10") (pintype "bidirectional"))
      (node (ref "X2") (pin "P10") (pinfunction "P10_P10") (pintype "bidirectional"))
      (node (ref "X3") (pin "P10") (pinfunction "P10_P10") (pintype "bidirectional"))
    )
    (net (code "51") (name "Net-(X1-PadP11)") (class "Default")
      (node (ref "X1") (pin "P11") (pinfunction "P11_P11") (pintype "bidirectional"))
      (node (ref "X2") (pin "P11") (pinfunction "P11_P11") (pintype "bidirectional"))
      (node (ref "X3") (pin "P11") (pinfunction "P11_P11") (pintype "bidirectional"))
    )
    (net (code "52") (name "Net-(X1-PadP12)") (class "Default")
      (node (ref "X1") (pin "P12") (pinfunction "P12_P12") (pintype "bidirectional"))
      (node (ref "X2") (pin "P12") (pinfunction "P12_P12") (pintype "bidirectional"))
      (node (ref "X3") (pin "P12") (pinfunction "P12_P12") (pintype "bidirectional"))
    )
    (net (code "53") (name "Net-(X1-PadP13)") (class "Default")
      (node (ref "X1") (pin "P13") (pinfunction "P13_P13") (pintype "bidirectional"))
      (node (ref "X2") (pin "P13") (pinfunction "P13_P13") (pintype "bidirectional"))
      (node (ref "X3") (pin "P13") (pinfunction "P13_P13") (pintype "bidirectional"))
    )
    (net (code "54") (name "Net-(X4-PadP1)") (class "Default")
      (node (ref "X4") (pin "P1") (pinfunction "P1_P1") (pintype "bidirectional"))
      (node (ref "X5") (pin "P1") (pinfunction "P1_P1") (pintype "bidirectional"))
      (node (ref "X6") (pin "P1") (pinfunction "P1_P1") (pintype "bidirectional"))
    )
    (net (code "55") (name "Net-(X4-PadP2)") (class "Default")
      (node (ref "X4") (pin "P2") (pinfunction "P2_P2") (pintype "bidirectional"))
      (node (ref "X5") (pin "P2") (pinfunction "P2_P2") (pintype "bidirectional"))
      (node (ref "X6") (pin "P2") (pinfunction "P2_P2") (pintype "bidirectional"))
    )
    (net (code "56") (name "Net-(X4-PadP3)") (class "Default")
      (node (ref "X4") (pin "P3") (pinfunction "P3_P3") (pintype "bidirectional"))
      (node (ref "X5") (pin "P3") (pinfunction "P3_P3") (pintype "bidirectional"))
      (node (ref "X6") (pin "P3") (pinfunction "P3_P3") (pintype "bidirectional"))
    )
    (net (code "57") (name "Net-(X4-PadP4)") (class "Default")
      (node (ref "X4") (pin "P4") (pinfunction "P4_P4") (pintype "bidirectional"))
      (node (ref "X5") (pin "P4") (pinfunction "P4_P4") (pintype "bidirectional"))
      (node (ref "X6") (pin "P4") (pinfunction "P4_P4") (pintype "bidirectional"))
    )
    (net (code "58") (name "Net-(X4-PadP5)") (class "Default")
      (node (ref "X4") (pin "P5") (pinfunction "P5_P5") (pintype "bidirectional"))
      (node (ref "X5") (pin "P5") (pinfunction "P5_P5") (pintype "bidirectional"))
      (node (ref "X6") (pin "P5") (pinfunction "P5_P5") (pintype "bidirectional"))
    )
    (net (code "59") (name "Net-(X4-PadP6)") (class "Default")
      (node (ref "X4") (pin "P6") (pinfunction "P6_P6") (pintype "bidirectional"))
      (node (ref "X5") (pin "P6") (pinfunction "P6_P6") (pintype "bidirectional"))
      (node (ref "X6") (pin "P6") (pinfunction "P6_P6") (pintype "bidirectional"))
    )
    (net (code "60") (name "Net-(X4-PadP7)") (class "Default")
      (node (ref "X4") (pin "P7") (pinfunction "P7_P7") (pintype "bidirectional"))
      (node (ref "X5") (pin "P7") (pinfunction "P7_P7") (pintype "bidirectional"))
      (node (ref "X6") (pin "P7") (pinfunction "P7_P7") (pintype "bidirectional"))
    )
    (net (code "61") (name "Net-(X4-PadP8)") (class "Default")
      (node (ref "X4") (pin "P8") (pinfunction "P8_P8") (pintype "bidirectional"))
      (node (ref "X5") (pin "P8") (pinfunction "P8_P8") (pintype "bidirectional"))
      (node (ref "X6") (pin "P8") (pinfunction "P8_P8") (pintype "bidirectional"))
    )
    (net (code "62") (name "Net-(X4-PadP9)") (class "Default")
      (node (ref "X4") (pin "P9") (pinfunction "P9_P9") (pintype "bidirectional"))
      (node (ref "X5") (pin "P9") (pinfunction "P9_P9") (pintype "bidirectional"))
      (node (ref "X6") (pin "P9") (pinfunction "P9_P9") (pintype "bidirectional"))
    )
    (net (code "63") (name "Net-(X4-PadP10)") (class "Default")
      (node (ref "X4") (pin "P10") (pinfunction "P10_P10") (pintype "bidirectional"))
      (node (ref "X5") (pin "P10") (pinfunction "P10_P10") (pintype "bidirectional"))
      (node (ref "X6") (pin "P10") (pinfunction "P10_P10") (pintype "bidirectional"))
    )
    (net (code "64") (name "Net-(X4-PadP11)") (class "Default")
      (node (ref "X4") (pin "P11") (pinfunction "P11_P11") (pintype "bidirectional"))
      (node (ref "X5") (pin "P11") (pinfunction "P11_P11") (pintype "bidirectional"))
      (node (ref "X6") (pin "P11") (pinfunction "P11_P11") (pintype "bidirectional"))
    )
    (net (code "65") (name "Net-(X4-PadP12)") (class "Default")
      (node (ref "X4") (pin "P12") (pinfunction "P12_P12") (pintype "bidirectional"))
      (node (ref "X5") (pin "P12") (pinfunction "P12_P12") (pintype "bidirectional"))
      (node (ref "X6") (pin "P12") (pinfunction "P12_P12") (pintype "bidirectional"))
    )
    (net (code "66") (name "Net-(X4-PadP13)") (class "Default")
      (node (ref "X4") (pin "P13") (pinfunction "P13_P13") (pintype "bidirectional"))
      (node (ref "X5") (pin "P13") (pinfunction "P13_P13") (pintype "bidirectional"))
      (node (ref "X6") (pin "P13") (pinfunction "P13_P13") (pintype "bidirectional"))
    )
    (net (code "67") (name "V_USB") (class "Default")
      (node (ref "J1") (pin "P1") (pinfunction "1_P1") (pintype "passive"))
      (node (ref "J1") (pin "P2") (pinfunction "2_P2") (pintype "passive"))
      (node (ref "J1") (pin "P3") (pinfunction "3_P3") (pintype "passive"))
      (node (ref "J1") (pin "P4") (pinfunction "4_P4") (pintype "passive"))
      (node (ref "U1") (pin "VUSB") (pinfunction "VUSB_VUSB") (pintype "bidirectional"))
      (node (ref "U2") (pin "VUSB") (pinfunction "VUSB_VUSB") (pintype "bidirectional"))
    )
    (net (code "68") (name "unconnected-(J2-1-PadP1)") (class "Default")
      (node (ref "J2") (pin "P1") (pinfunction "1_P1") (pintype "passive"))
    )
    (net (code "69") (name "unconnected-(J2-2-PadP2)") (class "Default")
      (node (ref "J2") (pin "P2") (pinfunction "2_P2") (pintype "passive"))
    )
    (net (code "70") (name "unconnected-(J2-3-PadP3)") (class "Default")
      (node (ref "J2") (pin "P3") (pinfunction "3_P3") (pintype "passive"))
    )
    (net (code "71") (name "unconnected-(J2-4-PadP4)") (class "Default")
      (node (ref "J2") (pin "P4") (pinfunction "4_P4") (pintype "passive"))
    )
    (net (code "72") (name "unconnected-(J3-1-PadP1)") (class "Default")
      (node (ref "J3") (pin "P1") (pinfunction "1_P1") (pintype "passive"))
    )
    (net (code "73") (name "unconnected-(J3-2-PadP2)") (class "Default")
      (node (ref "J3") (pin "P2") (pinfunction "2_P2") (pintype "passive"))
    )
    (net (code "74") (name "unconnected-(J3-3-PadP3)") (class "Default")
      (node (ref "J3") (pin "P3") (pinfunction "3_P3") (pintype "passive"))
    )
    (net (code "75") (name "unconnected-(J3-4-PadP4)") (class "Default")
      (node (ref "J3") (pin "P4") (pinfunction "4_P4") (pintype "passive"))
    )
    (net (code "76") (name "unconnected-(J4-1-PadP1)") (class "Default")
      (node (ref "J4") (pin "P1") (pinfunction "1_P1") (pintype "passive"))
    )
    (net (code "77") (name "unconnected-(J4-2-PadP2)") (class "Default")
      (node (ref "J4") (pin "P2") (pinfunction "2_P2") (pintype "passive"))
    )
    (net (code "78") (name "unconnected-(J4-3-PadP3)") (class "Default")
      (node (ref "J4") (pin "P3") (pinfunction "3_P3") (pintype "passive"))
    )
    (net (code "79") (name "unconnected-(J4-4-PadP4)") (class "Default")
      (node (ref "J4") (pin "P4") (pinfunction "4_P4") (pintype "passive"))
    )
  )
)
